# DISPLAY.net
KiCad netlist of a schematic drawn in Altium Designer
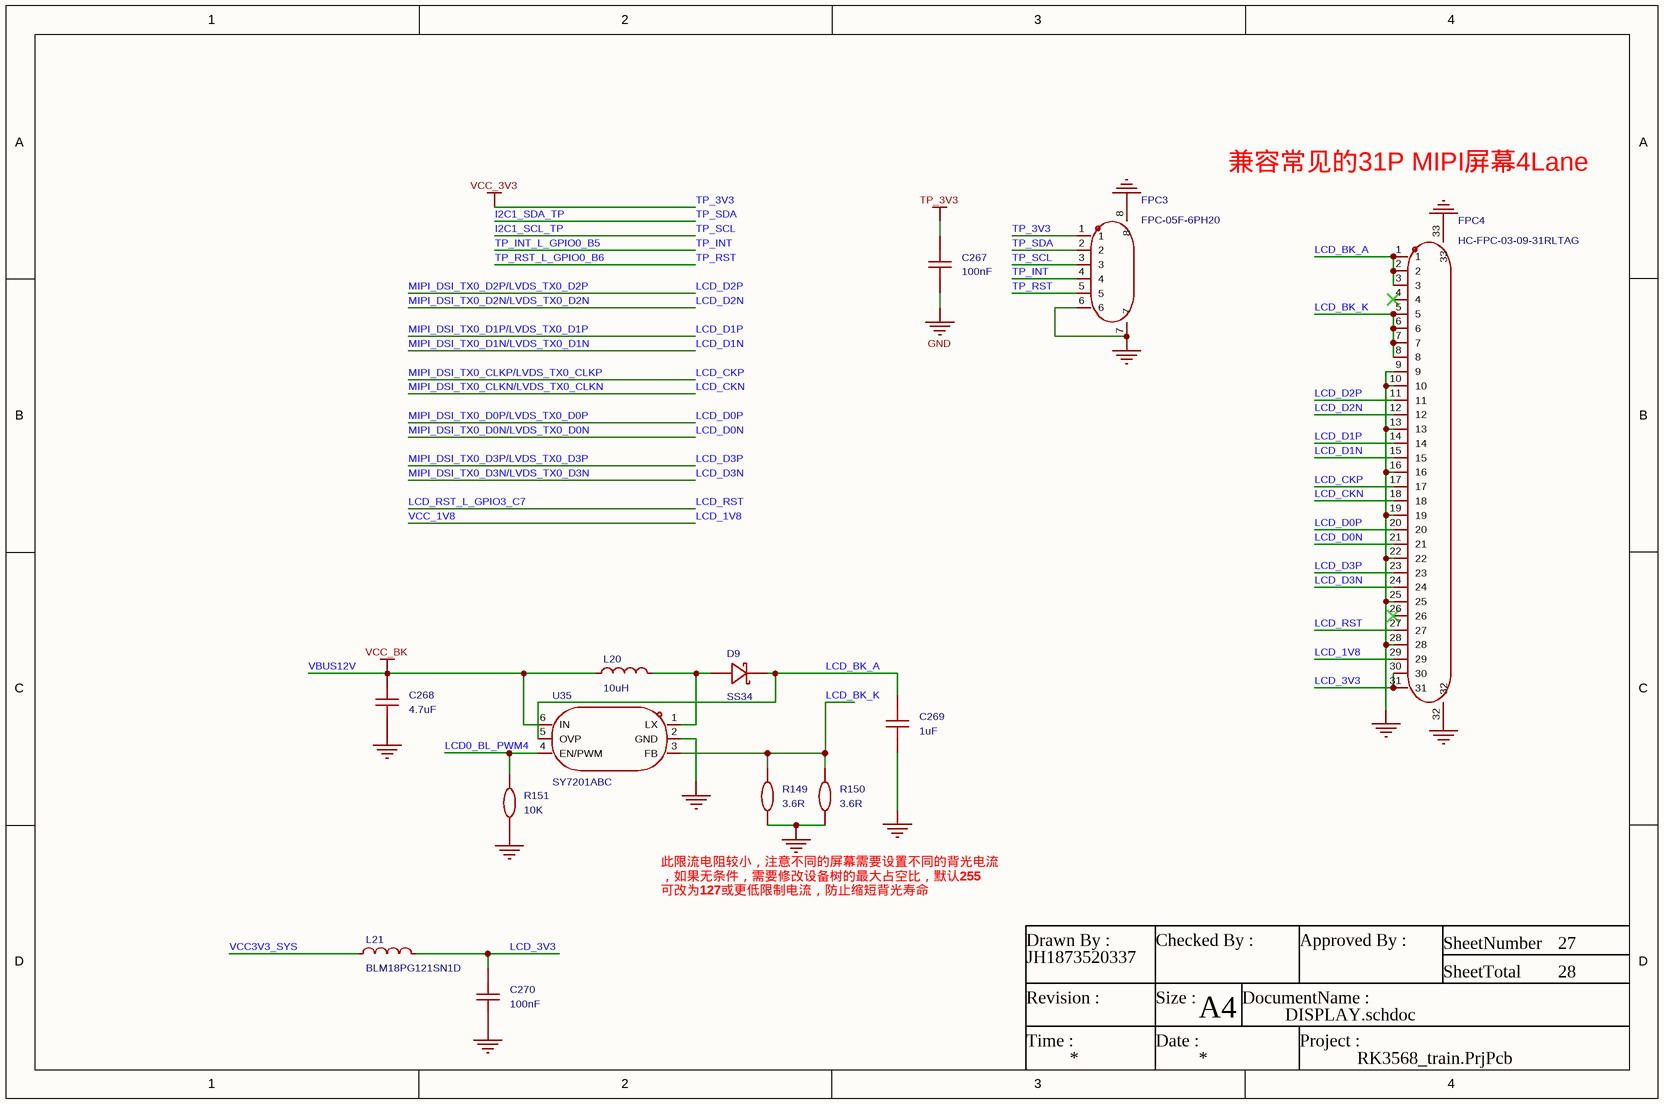
[diagram p0: DISPLAY.schdoc]

(export (version "E")
  (design (tool "Eeschema 10.0.6"))
  (components
    (comp (ref "C267")
      (value "100nF")
      (footprint "C0603")
      (libsource (lib "altium-import") (part "root_1_CAP_0603_"))
    )
    (comp (ref "C268")
      (value "4.7uF")
      (footprint "C0603")
      (libsource (lib "altium-import") (part "root_1_CAP_0603_"))
    )
    (comp (ref "C269")
      (value "1uF")
      (footprint "C0603")
      (libsource (lib "altium-import") (part "root_1_CAP_0603_"))
    )
    (comp (ref "C270")
      (value "100nF")
      (footprint "C0603")
      (libsource (lib "altium-import") (part "root_1_CAP_0603_"))
    )
    (comp (ref "D9")
      (value "SS34")
      (footprint "SMA_L4.3-W2.6-LS5.0-FD")
      (description "二极管配置:独立式;正向压降(Vf):550mV@3.0A;直流反向耐压(Vr):40V;平均整流电流(Io):3A;")
      (fields (field (name "MANUFACTURER") "宏迦橙"))
      (libsource (lib "altium-import") (part "root_0_SS34_C7420365_"))
    )
    (comp (ref "FPC3")
      (value "FPC-05F-6PH20")
      (footprint "FPC-SMD_6P-P0.50_XUNPU_FPC-05F-6PH20")
      (description "锁定特性:翻盖式;触点类型:下接;触点数量:6P;间距:0.5mm;安装类型:卧贴;工作温度范围:-25℃~+85℃;")
      (fields (field (name "MANUFACTURER") "XUNPU(讯普)"))
      (libsource (lib "altium-import") (part "root_0_FPC-05F-6PH20_"))
    )
    (comp (ref "FPC4")
      (value "HC-FPC-03-09-31RLTAG")
      (footprint "FPC-SMD_31P-P0.30_HC-FPC-03-09-31RLTAG")
      (description "锁定特性:翻盖式;触点类型:下接;触点数量:31P;间距:0.3mm;安装方式:卧贴;工作温度:-55℃~+85℃;")
      (fields (field (name "MANUFACTURER") "HCTL(华灿天禄)"))
      (libsource (lib "altium-import") (part "root_0_HC-FPC-03-09-31RLTAG_"))
    )
    (comp (ref "L20")
      (value "10uH")
      (footprint "IND-SMD_L2.5-W2.0")
      (description "电感值:10uH;精度:±20%;额定电流:1.2A;饱和电流(Isat):1.6A;类型:一体成型电感;")
      (fields
        (field (name "MANUFACTURER") "cjiang(长江微电)")
        (field (name "MANUFACTURERPART") "FTC252012S100MBCA")
      )
      (libsource (lib "altium-import") (part "root_0_FTC252012S100MBCA_"))
    )
    (comp (ref "L21")
      (value "BLM18PG121SN1D")
      (footprint "L0603")
      (description "标称阻抗@测试频率:120Ω@100MHz;误差:±25%;直流电阻(RDC):50mΩ;")
      (fields (field (name "MANUFACTURER") "muRata(村田)") (field (name "TOLERANCE") "±25%"))
      (libsource (lib "altium-import") (part "root_0_BLM18PG121SN1D_"))
    )
    (comp (ref "R149")
      (value "3.6R")
      (footprint "R0603")
      (libsource (lib "altium-import") (part "root_1_Res_0603_"))
    )
    (comp (ref "R150")
      (value "3.6R")
      (footprint "R0603")
      (libsource (lib "altium-import") (part "root_1_Res_0603_"))
    )
    (comp (ref "R151")
      (value "10K")
      (footprint "R0402")
      (libsource (lib "altium-import") (part "root_1_Res_0402_"))
    )
    (comp (ref "U35")
      (value "SY7201ABC")
      (footprint "SOT-23-6_L2.9-W1.6-P0.95-LS2.8-BR")
      (description "拓扑结构:升压;")
      (fields (field (name "MANUFACTURER") "Silergy(矽力杰)"))
      (libsource (lib "altium-import") (part "root_0_mirrored_SY7201ABC_"))
    )
  )
  (nets
    (net (code "1") (name "/I2C1_SCL_TP") (class "Default")
      (node (ref "FPC3") (pin "3") (pinfunction "3_3") (pintype "passive"))
    )
    (net (code "2") (name "/I2C1_SDA_TP") (class "Default")
      (node (ref "FPC3") (pin "2") (pinfunction "2_2") (pintype "passive"))
    )
    (net (code "3") (name "/LCD0_BL_PWM4") (class "Default")
      (node (ref "R151") (pin "2") (pinfunction "2_2") (pintype "passive"))
      (node (ref "U35") (pin "4") (pinfunction "EN/PWM_4") (pintype "passive"))
    )
    (net (code "4") (name "/LCD_1V8") (class "Default")
      (node (ref "FPC4") (pin "29") (pinfunction "29_29") (pintype "passive"))
    )
    (net (code "5") (name "/LCD_3V3") (class "Default")
      (node (ref "C270") (pin "2") (pinfunction "2_2") (pintype "passive"))
      (node (ref "FPC4") (pin "30") (pinfunction "30_30") (pintype "passive"))
      (node (ref "FPC4") (pin "31") (pinfunction "31_31") (pintype "passive"))
      (node (ref "L21") (pin "2") (pinfunction "2_2") (pintype "passive"))
    )
    (net (code "6") (name "/LCD_BK_A") (class "Default")
      (node (ref "C269") (pin "2") (pinfunction "2_2") (pintype "passive"))
      (node (ref "D9") (pin "2") (pinfunction "K_2") (pintype "passive"))
      (node (ref "FPC4") (pin "1") (pinfunction "1_1") (pintype "passive"))
      (node (ref "FPC4") (pin "2") (pinfunction "2_2") (pintype "passive"))
      (node (ref "FPC4") (pin "3") (pinfunction "3_3") (pintype "passive"))
      (node (ref "U35") (pin "5") (pinfunction "OVP_5") (pintype "passive"))
    )
    (net (code "7") (name "/LCD_BK_K") (class "Default")
      (node (ref "FPC4") (pin "5") (pinfunction "5_5") (pintype "passive"))
      (node (ref "FPC4") (pin "6") (pinfunction "6_6") (pintype "passive"))
      (node (ref "FPC4") (pin "7") (pinfunction "7_7") (pintype "passive"))
      (node (ref "FPC4") (pin "8") (pinfunction "8_8") (pintype "passive"))
      (node (ref "R149") (pin "2") (pinfunction "2_2") (pintype "passive"))
      (node (ref "R150") (pin "2") (pinfunction "2_2") (pintype "passive"))
      (node (ref "U35") (pin "3") (pinfunction "FB_3") (pintype "passive"))
    )
    (net (code "8") (name "/LCD_CKN") (class "Default")
      (node (ref "FPC4") (pin "18") (pinfunction "18_18") (pintype "passive"))
    )
    (net (code "9") (name "/LCD_CKP") (class "Default")
      (node (ref "FPC4") (pin "17") (pinfunction "17_17") (pintype "passive"))
    )
    (net (code "10") (name "/LCD_D0N") (class "Default")
      (node (ref "FPC4") (pin "21") (pinfunction "21_21") (pintype "passive"))
    )
    (net (code "11") (name "/LCD_D0P") (class "Default")
      (node (ref "FPC4") (pin "20") (pinfunction "20_20") (pintype "passive"))
    )
    (net (code "12") (name "/LCD_D1N") (class "Default")
      (node (ref "FPC4") (pin "15") (pinfunction "15_15") (pintype "passive"))
    )
    (net (code "13") (name "/LCD_D1P") (class "Default")
      (node (ref "FPC4") (pin "14") (pinfunction "14_14") (pintype "passive"))
    )
    (net (code "14") (name "/LCD_D2N") (class "Default")
      (node (ref "FPC4") (pin "12") (pinfunction "12_12") (pintype "passive"))
    )
    (net (code "15") (name "/LCD_D2P") (class "Default")
      (node (ref "FPC4") (pin "11") (pinfunction "11_11") (pintype "passive"))
    )
    (net (code "16") (name "/LCD_D3N") (class "Default")
      (node (ref "FPC4") (pin "24") (pinfunction "24_24") (pintype "passive"))
    )
    (net (code "17") (name "/LCD_D3P") (class "Default")
      (node (ref "FPC4") (pin "23") (pinfunction "23_23") (pintype "passive"))
    )
    (net (code "18") (name "/LCD_RST") (class "Default")
      (node (ref "FPC4") (pin "27") (pinfunction "27_27") (pintype "passive"))
    )
    (net (code "19") (name "/TP_INT") (class "Default")
      (node (ref "FPC3") (pin "4") (pinfunction "4_4") (pintype "passive"))
    )
    (net (code "20") (name "/TP_RST") (class "Default")
      (node (ref "FPC3") (pin "5") (pinfunction "5_5") (pintype "passive"))
    )
    (net (code "21") (name "/VCC3V3_SYS") (class "Default")
      (node (ref "L21") (pin "1") (pinfunction "1_1") (pintype "passive"))
    )
    (net (code "22") (name "GND") (class "Default")
      (node (ref "C267") (pin "1") (pinfunction "1_1") (pintype "passive"))
      (node (ref "C268") (pin "1") (pinfunction "1_1") (pintype "passive"))
      (node (ref "C269") (pin "1") (pinfunction "1_1") (pintype "passive"))
      (node (ref "C270") (pin "1") (pinfunction "1_1") (pintype "passive"))
      (node (ref "FPC3") (pin "6") (pinfunction "6_6") (pintype "passive"))
      (node (ref "FPC3") (pin "7") (pinfunction "7_7") (pintype "passive"))
      (node (ref "FPC3") (pin "8") (pinfunction "8_8") (pintype "passive"))
      (node (ref "FPC4") (pin "10") (pinfunction "10_10") (pintype "passive"))
      (node (ref "FPC4") (pin "13") (pinfunction "13_13") (pintype "passive"))
      (node (ref "FPC4") (pin "16") (pinfunction "16_16") (pintype "passive"))
      (node (ref "FPC4") (pin "19") (pinfunction "19_19") (pintype "passive"))
      (node (ref "FPC4") (pin "22") (pinfunction "22_22") (pintype "passive"))
      (node (ref "FPC4") (pin "25") (pinfunction "25_25") (pintype "passive"))
      (node (ref "FPC4") (pin "28") (pinfunction "28_28") (pintype "passive"))
      (node (ref "FPC4") (pin "32") (pinfunction "32_32") (pintype "passive"))
      (node (ref "FPC4") (pin "33") (pinfunction "33_33") (pintype "passive"))
      (node (ref "FPC4") (pin "9") (pinfunction "9_9") (pintype "passive"))
      (node (ref "R149") (pin "1") (pinfunction "1_1") (pintype "passive"))
      (node (ref "R150") (pin "1") (pinfunction "1_1") (pintype "passive"))
      (node (ref "R151") (pin "1") (pinfunction "1_1") (pintype "passive"))
      (node (ref "U35") (pin "2") (pinfunction "GND_2") (pintype "passive"))
    )
    (net (code "23") (name "Net-(D9-A)") (class "Default")
      (node (ref "D9") (pin "1") (pinfunction "A_1") (pintype "passive"))
      (node (ref "L20") (pin "1") (pinfunction "1_1") (pintype "passive"))
      (node (ref "U35") (pin "1") (pinfunction "LX_1") (pintype "passive"))
    )
    (net (code "24") (name "TP_3V3") (class "Default")
      (node (ref "C267") (pin "2") (pinfunction "2_2") (pintype "passive"))
      (node (ref "FPC3") (pin "1") (pinfunction "1_1") (pintype "passive"))
    )
    (net (code "25") (name "VCC_BK") (class "Default")
      (node (ref "C268") (pin "2") (pinfunction "2_2") (pintype "passive"))
      (node (ref "L20") (pin "2") (pinfunction "2_2") (pintype "passive"))
      (node (ref "U35") (pin "6") (pinfunction "IN_6") (pintype "passive"))
    )
    (net (code "26") (name "unconnected-(FPC4-Pad4)") (class "Default")
      (node (ref "FPC4") (pin "4") (pinfunction "4_4") (pintype "passive+no_connect"))
    )
    (net (code "27") (name "unconnected-(FPC4-Pad26)") (class "Default")
      (node (ref "FPC4") (pin "26") (pinfunction "26_26") (pintype "passive+no_connect"))
    )
  )
)
